# Row_Alt_-_Copy.net
KiCad netlist of a schematic drawn in Altium Designer
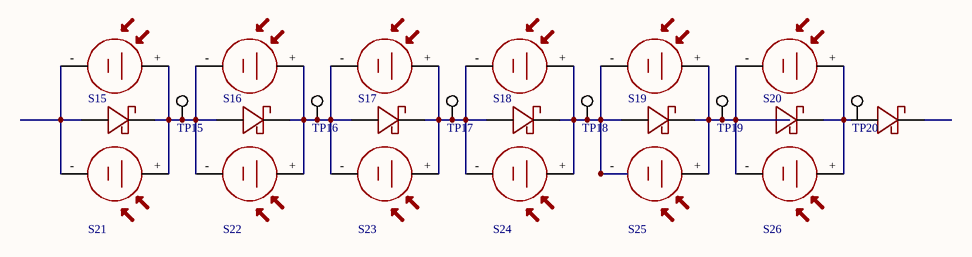
[diagram p0: Row(Alt) - Copy.SchDoc]

(export (version "E")
  (design (tool "Eeschema 10.0.6"))
  (components
    (comp (ref "D17")
      (value "SCHOTTKY_DIODE_B120-FDICT-NDSCHOTTKY_DIODE_B120-FDICT-ND")
      (footprint "SB_DIODE")
      (fields (field (name "LIBRARYNAME") "Solar_Fadi"))
      (libsource (lib "SchLib") (part "SCHOTTKY_DIODE_B120-FDICT-NDSCHOTTKY_DIODE_B120-FDICT-ND"))
    )
    (comp (ref "D18")
      (value "SCHOTTKY_DIODE_B120-FDICT-NDSCHOTTKY_DIODE_B120-FDICT-ND")
      (footprint "SB_DIODE")
      (fields (field (name "LIBRARYNAME") "Solar_Fadi"))
      (libsource (lib "SchLib") (part "SCHOTTKY_DIODE_B120-FDICT-NDSCHOTTKY_DIODE_B120-FDICT-ND"))
    )
    (comp (ref "D19")
      (value "SCHOTTKY_DIODE_B120-FDICT-NDSCHOTTKY_DIODE_B120-FDICT-ND")
      (footprint "SB_DIODE")
      (fields (field (name "LIBRARYNAME") "Solar_Fadi"))
      (libsource (lib "SchLib") (part "SCHOTTKY_DIODE_B120-FDICT-NDSCHOTTKY_DIODE_B120-FDICT-ND"))
    )
    (comp (ref "D20")
      (value "SCHOTTKY_DIODE_B120-FDICT-NDSCHOTTKY_DIODE_B120-FDICT-ND")
      (footprint "SB_DIODE")
      (fields (field (name "LIBRARYNAME") "Solar_Fadi"))
      (libsource (lib "SchLib") (part "SCHOTTKY_DIODE_B120-FDICT-NDSCHOTTKY_DIODE_B120-FDICT-ND"))
    )
    (comp (ref "D21")
      (value "SCHOTTKY_DIODE_B120-FDICT-NDSCHOTTKY_DIODE_B120-FDICT-ND")
      (footprint "SB_DIODE")
      (fields (field (name "LIBRARYNAME") "Solar_Fadi"))
      (libsource (lib "SchLib") (part "SCHOTTKY_DIODE_B120-FDICT-NDSCHOTTKY_DIODE_B120-FDICT-ND"))
    )
    (comp (ref "D22")
      (value "SCHOTTKY_DIODE_B120-FDICT-NDSCHOTTKY_DIODE_B120-FDICT-ND")
      (footprint "SB_DIODE")
      (fields (field (name "LIBRARYNAME") "Solar_Fadi"))
      (libsource (lib "") (part "SCHOTTKY_DIODE_B120-FDICT-NDSCHOTTKY_DIODE_B120-FDICT-ND_1"))
    )
    (comp (ref "D23")
      (value "SCHOTTKY_DIODE_B120-FDICT-NDSCHOTTKY_DIODE_B120-FDICT-ND")
      (footprint "SB_DIODE")
      (fields (field (name "LIBRARYNAME") "Solar_Fadi"))
      (libsource (lib "SchLib") (part "SCHOTTKY_DIODE_B120-FDICT-NDSCHOTTKY_DIODE_B120-FDICT-ND"))
    )
    (comp (ref "S15")
      (value "SOLAR_CELL")
      (footprint "SOLAR_CELL")
      (libsource (lib "SchLib") (part "SOLAR_CELL"))
    )
    (comp (ref "S16")
      (value "SOLAR_CELL")
      (footprint "SOLAR_CELL")
      (libsource (lib "SchLib") (part "SOLAR_CELL"))
    )
    (comp (ref "S17")
      (value "SOLAR_CELL")
      (footprint "SOLAR_CELL")
      (libsource (lib "SchLib") (part "SOLAR_CELL"))
    )
    (comp (ref "S18")
      (value "SOLAR_CELL")
      (footprint "SOLAR_CELL")
      (libsource (lib "SchLib") (part "SOLAR_CELL"))
    )
    (comp (ref "S19")
      (value "SOLAR_CELL")
      (footprint "SOLAR_CELL")
      (libsource (lib "SchLib") (part "SOLAR_CELL"))
    )
    (comp (ref "S20")
      (value "SOLAR_CELL")
      (footprint "SOLAR_CELL")
      (libsource (lib "SchLib") (part "SOLAR_CELL"))
    )
    (comp (ref "S21")
      (value "SOLAR_CELL")
      (footprint "SOLAR_CELL")
      (libsource (lib "SchLib") (part "SOLAR_CELL"))
    )
    (comp (ref "S22")
      (value "SOLAR_CELL")
      (footprint "SOLAR_CELL")
      (libsource (lib "SchLib") (part "SOLAR_CELL"))
    )
    (comp (ref "S23")
      (value "SOLAR_CELL")
      (footprint "SOLAR_CELL")
      (libsource (lib "SchLib") (part "SOLAR_CELL"))
    )
    (comp (ref "S24")
      (value "SOLAR_CELL")
      (footprint "SOLAR_CELL")
      (libsource (lib "SchLib") (part "SOLAR_CELL"))
    )
    (comp (ref "S25")
      (value "SOLAR_CELL")
      (footprint "SOLAR_CELL")
      (libsource (lib "SchLib") (part "SOLAR_CELL"))
    )
    (comp (ref "S26")
      (value "SOLAR_CELL")
      (footprint "SOLAR_CELL")
      (libsource (lib "SchLib") (part "SOLAR_CELL"))
    )
    (comp (ref "TP15")
      (value "TEST_POINT")
      (footprint "TEST_POINT")
      (libsource (lib "SchLib") (part "TEST_POINT"))
    )
    (comp (ref "TP16")
      (value "TEST_POINT")
      (footprint "TEST_POINT")
      (libsource (lib "SchLib") (part "TEST_POINT"))
    )
    (comp (ref "TP17")
      (value "TEST_POINT")
      (footprint "TEST_POINT")
      (libsource (lib "SchLib") (part "TEST_POINT"))
    )
    (comp (ref "TP18")
      (value "TEST_POINT")
      (footprint "TEST_POINT")
      (libsource (lib "SchLib") (part "TEST_POINT"))
    )
    (comp (ref "TP19")
      (value "TEST_POINT")
      (footprint "TEST_POINT")
      (libsource (lib "SchLib") (part "TEST_POINT"))
    )
    (comp (ref "TP20")
      (value "TEST_POINT")
      (footprint "TEST_POINT")
      (libsource (lib "SchLib") (part "TEST_POINT"))
    )
  )
  (nets
    (net (code "1") (name "Net-(D17-PadNEG)") (class "Default")
      (node (ref "D17") (pin "NEG") (pinfunction "NEG_NEG") (pintype "passive"))
      (node (ref "D18") (pin "POS") (pinfunction "POS_POS") (pintype "passive"))
      (node (ref "S15") (pin "+") (pinfunction "+_+") (pintype "passive"))
      (node (ref "S16") (pin "-") (pinfunction "-_-") (pintype "passive"))
      (node (ref "S21") (pin "+") (pinfunction "+_+") (pintype "passive"))
      (node (ref "S22") (pin "-") (pinfunction "-_-") (pintype "passive"))
      (node (ref "TP15") (pin "38") (pinfunction "38_38") (pintype "passive"))
    )
    (net (code "2") (name "Net-(D17-PadPOS)") (class "Default")
      (node (ref "D17") (pin "POS") (pinfunction "POS_POS") (pintype "passive"))
      (node (ref "S15") (pin "-") (pinfunction "-_-") (pintype "passive"))
      (node (ref "S21") (pin "-") (pinfunction "-_-") (pintype "passive"))
    )
    (net (code "3") (name "Net-(D18-PadNEG)") (class "Default")
      (node (ref "D18") (pin "NEG") (pinfunction "NEG_NEG") (pintype "passive"))
      (node (ref "D19") (pin "POS") (pinfunction "POS_POS") (pintype "passive"))
      (node (ref "S16") (pin "+") (pinfunction "+_+") (pintype "passive"))
      (node (ref "S17") (pin "-") (pinfunction "-_-") (pintype "passive"))
      (node (ref "S22") (pin "+") (pinfunction "+_+") (pintype "passive"))
      (node (ref "S23") (pin "-") (pinfunction "-_-") (pintype "passive"))
      (node (ref "TP16") (pin "38") (pinfunction "38_38") (pintype "passive"))
    )
    (net (code "4") (name "Net-(D19-PadNEG)") (class "Default")
      (node (ref "D19") (pin "NEG") (pinfunction "NEG_NEG") (pintype "passive"))
      (node (ref "D20") (pin "POS") (pinfunction "POS_POS") (pintype "passive"))
      (node (ref "S17") (pin "+") (pinfunction "+_+") (pintype "passive"))
      (node (ref "S18") (pin "-") (pinfunction "-_-") (pintype "passive"))
      (node (ref "S23") (pin "+") (pinfunction "+_+") (pintype "passive"))
      (node (ref "S24") (pin "-") (pinfunction "-_-") (pintype "passive"))
      (node (ref "TP17") (pin "38") (pinfunction "38_38") (pintype "passive"))
    )
    (net (code "5") (name "Net-(D20-PadNEG)") (class "Default")
      (node (ref "D20") (pin "NEG") (pinfunction "NEG_NEG") (pintype "passive"))
      (node (ref "D21") (pin "POS") (pinfunction "POS_POS") (pintype "passive"))
      (node (ref "S18") (pin "+") (pinfunction "+_+") (pintype "passive"))
      (node (ref "S19") (pin "-") (pinfunction "-_-") (pintype "passive"))
      (node (ref "S24") (pin "+") (pinfunction "+_+") (pintype "passive"))
      (node (ref "S25") (pin "-") (pinfunction "-_-") (pintype "passive"))
      (node (ref "TP18") (pin "38") (pinfunction "38_38") (pintype "passive"))
    )
    (net (code "6") (name "Net-(D21-PadNEG)") (class "Default")
      (node (ref "D21") (pin "NEG") (pinfunction "NEG_NEG") (pintype "passive"))
      (node (ref "S19") (pin "+") (pinfunction "+_+") (pintype "passive"))
      (node (ref "S20") (pin "-") (pinfunction "-_-") (pintype "passive"))
      (node (ref "S25") (pin "+") (pinfunction "+_+") (pintype "passive"))
      (node (ref "S26") (pin "-") (pinfunction "-_-") (pintype "passive"))
      (node (ref "TP19") (pin "38") (pinfunction "38_38") (pintype "passive"))
    )
    (net (code "7") (name "Net-(D22-PadNEG)") (class "Default")
      (node (ref "D22") (pin "NEG") (pinfunction "NEG_NEG") (pintype "passive"))
      (node (ref "D23") (pin "POS") (pinfunction "POS_POS") (pintype "passive"))
      (node (ref "S20") (pin "+") (pinfunction "+_+") (pintype "passive"))
      (node (ref "S26") (pin "+") (pinfunction "+_+") (pintype "passive"))
    )
    (net (code "8") (name "unconnected-(D23-PadNEG)") (class "Default")
      (node (ref "D23") (pin "NEG") (pinfunction "NEG_NEG") (pintype "passive"))
    )
    (net (code "9") (name "unconnected-(TP20-Pad38)") (class "Default")
      (node (ref "TP20") (pin "38") (pinfunction "38_38") (pintype "passive"))
    )
  )
)
